# OutputBuffer.net
KiCad netlist of a schematic drawn in Altium Designer
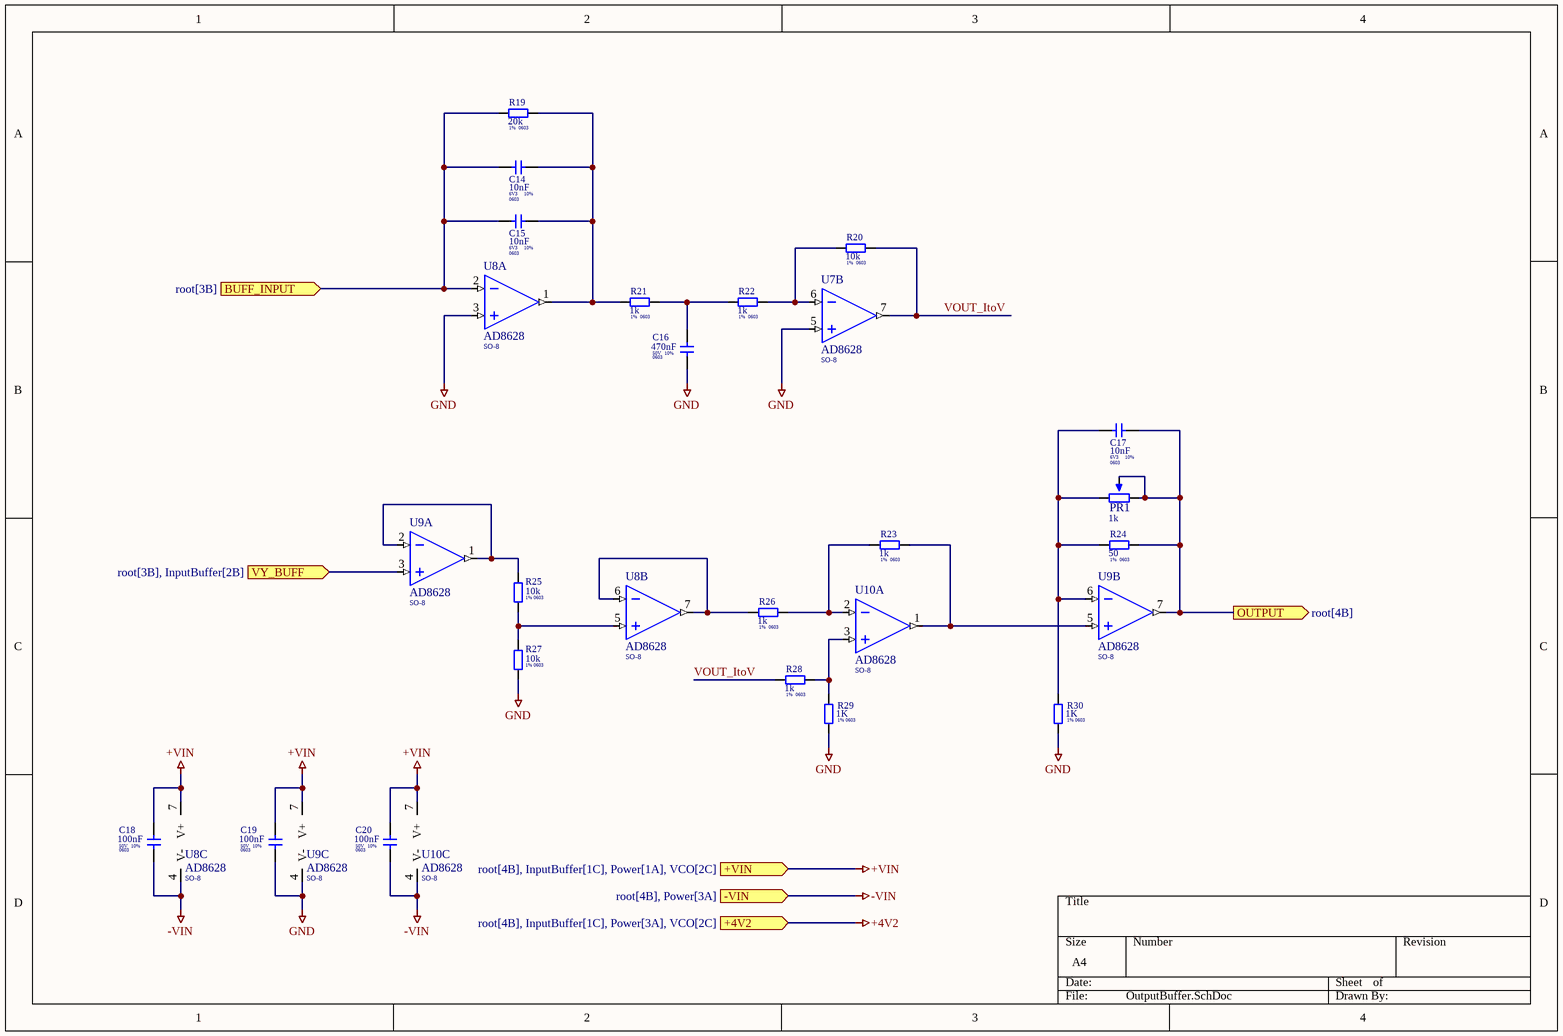
[diagram p0: OutputBuffer.SchDoc]

(export (version "E")
  (design (tool "Eeschema 10.0.6"))
  (components
    (comp (ref "C14")
      (value "10nF")
      (footprint "CAPC1608X06M")
      (fields
        (field (name "VOLTAGE") "6V3")
        (field (name "TOLERANT") "10%")
        (field (name "PACKAGE") "0603")
        (field (name "Comment") "10nF/6V3")
      )
      (libsource (lib "Falcon-SchMain-Lib") (part "C"))
    )
    (comp (ref "C15")
      (value "10nF")
      (footprint "CAPC1608X06M")
      (fields
        (field (name "VOLTAGE") "6V3")
        (field (name "TOLERANT") "10%")
        (field (name "PACKAGE") "0603")
        (field (name "Comment") "10nF/6V3")
      )
      (libsource (lib "Falcon-SchMain-Lib") (part "C"))
    )
    (comp (ref "C16")
      (value "470nF")
      (footprint "CAPC1608X06M")
      (fields
        (field (name "VOLTAGE") "50V")
        (field (name "TOLERANT") "10%")
        (field (name "PACKAGE") "0603")
        (field (name "Comment") "470nF/50V")
      )
      (libsource (lib "Falcon-SchMain-Lib") (part "C"))
    )
    (comp (ref "C17")
      (value "10nF")
      (footprint "CAPC1608X06M")
      (fields
        (field (name "VOLTAGE") "6V3")
        (field (name "TOLERANT") "10%")
        (field (name "PACKAGE") "0603")
        (field (name "Comment") "10nF/6V3")
      )
      (libsource (lib "Falcon-SchMain-Lib") (part "C"))
    )
    (comp (ref "C18")
      (value "100nF")
      (footprint "CAPC1608X06M")
      (fields
        (field (name "VOLTAGE") "50V")
        (field (name "TOLERANT") "10%")
        (field (name "PACKAGE") "0603")
        (field (name "Comment") "100nF/50V")
      )
      (libsource (lib "Falcon-SchMain-Lib") (part "C"))
    )
    (comp (ref "C19")
      (value "100nF")
      (footprint "CAPC1608X06M")
      (fields
        (field (name "VOLTAGE") "50V")
        (field (name "TOLERANT") "10%")
        (field (name "PACKAGE") "0603")
        (field (name "Comment") "100nF/50V")
      )
      (libsource (lib "Falcon-SchMain-Lib") (part "C"))
    )
    (comp (ref "C20")
      (value "100nF")
      (footprint "CAPC1608X06M")
      (fields
        (field (name "VOLTAGE") "50V")
        (field (name "TOLERANT") "10%")
        (field (name "PACKAGE") "0603")
        (field (name "Comment") "100nF/50V")
      )
      (libsource (lib "Falcon-SchMain-Lib") (part "C"))
    )
    (comp (ref "PR1") (value "1k") (footprint "PR_TRIM") (libsource (lib "Falcon-SchMain-Lib") (part "R_PR")))
    (comp (ref "R19")
      (value "20k")
      (footprint "RESC1608X06L")
      (fields
        (field (name "PACKAGE") "0603")
        (field (name "TOLERANCE") "1%")
        (field (name "Comment") "20k 1%")
      )
      (libsource (lib "Falcon-SchMain-Lib") (part "R"))
    )
    (comp (ref "R20")
      (value "10k")
      (footprint "RESC1608X06L")
      (fields
        (field (name "PACKAGE") "0603")
        (field (name "TOLERANCE") "1%")
        (field (name "Comment") "10k 1%")
      )
      (libsource (lib "Falcon-SchMain-Lib") (part "R"))
    )
    (comp (ref "R21")
      (value "1k")
      (footprint "RESC1608X06L")
      (fields
        (field (name "PACKAGE") "0603")
        (field (name "TOLERANCE") "1%")
        (field (name "Comment") "1k 1%")
      )
      (libsource (lib "Falcon-SchMain-Lib") (part "R"))
    )
    (comp (ref "R22")
      (value "1k")
      (footprint "RESC1608X06L")
      (fields
        (field (name "PACKAGE") "0603")
        (field (name "TOLERANCE") "1%")
        (field (name "Comment") "1k 1%")
      )
      (libsource (lib "Falcon-SchMain-Lib") (part "R"))
    )
    (comp (ref "R23")
      (value "1k")
      (footprint "RESC1608X06L")
      (fields
        (field (name "PACKAGE") "0603")
        (field (name "TOLERANCE") "1%")
        (field (name "Comment") "1k 1%")
      )
      (libsource (lib "Falcon-SchMain-Lib") (part "R"))
    )
    (comp (ref "R24")
      (value "50")
      (footprint "RESC1608X06L")
      (fields
        (field (name "PACKAGE") "0603")
        (field (name "TOLERANCE") "1%")
        (field (name "Comment") "50 1%")
      )
      (libsource (lib "Falcon-SchMain-Lib") (part "R"))
    )
    (comp (ref "R25")
      (value "10k")
      (footprint "RESC1608X06L")
      (fields
        (field (name "PACKAGE") "0603")
        (field (name "TOLERANCE") "1%")
        (field (name "Comment") "10k 1%")
      )
      (libsource (lib "") (part "R_1"))
    )
    (comp (ref "R26")
      (value "1k")
      (footprint "RESC1608X06L")
      (fields
        (field (name "PACKAGE") "0603")
        (field (name "TOLERANCE") "1%")
        (field (name "Comment") "1k 1%")
      )
      (libsource (lib "Falcon-SchMain-Lib") (part "R"))
    )
    (comp (ref "R27")
      (value "10k")
      (footprint "RESC1608X06L")
      (fields
        (field (name "PACKAGE") "0603")
        (field (name "TOLERANCE") "1%")
        (field (name "Comment") "10k 1%")
      )
      (libsource (lib "") (part "R_1"))
    )
    (comp (ref "R28")
      (value "1k")
      (footprint "RESC1608X06L")
      (fields
        (field (name "PACKAGE") "0603")
        (field (name "TOLERANCE") "1%")
        (field (name "Comment") "1k 1%")
      )
      (libsource (lib "Falcon-SchMain-Lib") (part "R"))
    )
    (comp (ref "R29")
      (value "1K")
      (footprint "RESC1608X06L")
      (fields
        (field (name "PACKAGE") "0603")
        (field (name "TOLERANCE") "1%")
        (field (name "Comment") "1K 1%")
      )
      (libsource (lib "") (part "R_1"))
    )
    (comp (ref "R30")
      (value "1K")
      (footprint "RESC1608X06L")
      (fields
        (field (name "PACKAGE") "0603")
        (field (name "TOLERANCE") "1%")
        (field (name "Comment") "1K 1%")
      )
      (libsource (lib "") (part "R_1"))
    )
    (comp (ref "U7")
      (value "AD8628")
      (footprint "SOIC127P600X170-8N")
      (description "Zero-Drift, Single-Supply, Rail-to-Rail Input/Output Operational Amplifier")
      (fields (field (name "PACKAGE") "SO-8"))
      (libsource (lib "Falcon-SchMain-Lib") (part "AD8628ARZ"))
    )
    (comp (ref "U8")
      (value "AD8628")
      (footprint "SOIC127P600X170-8N")
      (description "Zero-Drift, Single-Supply, Rail-to-Rail Input/Output Operational Amplifier")
      (fields (field (name "PACKAGE") "SO-8"))
      (libsource (lib "Falcon-SchMain-Lib") (part "AD8628ARZ"))
    )
    (comp (ref "U9")
      (value "AD8628")
      (footprint "SOIC127P600X170-8N")
      (description "Zero-Drift, Single-Supply, Rail-to-Rail Input/Output Operational Amplifier")
      (fields (field (name "PACKAGE") "SO-8"))
      (libsource (lib "Falcon-SchMain-Lib") (part "AD8628ARZ"))
    )
    (comp (ref "U10")
      (value "AD8628")
      (footprint "SOIC127P600X170-8N")
      (description "Zero-Drift, Single-Supply, Rail-to-Rail Input/Output Operational Amplifier")
      (fields (field (name "PACKAGE") "SO-8"))
      (libsource (lib "Falcon-SchMain-Lib") (part "AD8628ARZ"))
    )
  )
  (nets
    (net (code "2") (name "+VIN") (class "Default")
      (node (ref "C18") (pin "2") (pinfunction "2_2") (pintype "passive"))
      (node (ref "C19") (pin "2") (pinfunction "2_2") (pintype "passive"))
      (node (ref "C20") (pin "2") (pinfunction "2_2") (pintype "passive"))
      (node (ref "U10") (pin "7") (pinfunction "V+_7") (pintype "power_in"))
      (node (ref "U8") (pin "7") (pinfunction "V+_7") (pintype "power_in"))
      (node (ref "U9") (pin "7") (pinfunction "V+_7") (pintype "power_in"))
    )
    (net (code "3") (name "-VIN") (class "Default")
      (node (ref "C18") (pin "1") (pinfunction "1_1") (pintype "passive"))
      (node (ref "C20") (pin "1") (pinfunction "1_1") (pintype "passive"))
      (node (ref "U10") (pin "4") (pinfunction "V-_4") (pintype "power_in"))
      (node (ref "U8") (pin "4") (pinfunction "V-_4") (pintype "power_in"))
    )
    (net (code "4") (name "/BUFF_INPUT") (class "Default")
      (node (ref "C14") (pin "1") (pinfunction "1_1") (pintype "passive"))
      (node (ref "C15") (pin "1") (pinfunction "1_1") (pintype "passive"))
      (node (ref "R19") (pin "1") (pinfunction "1_1") (pintype "passive"))
      (node (ref "U8") (pin "2") (pinfunction "IN-_2") (pintype "input"))
    )
    (net (code "5") (name "/OUTPUT") (class "Default")
      (node (ref "C17") (pin "2") (pinfunction "2_2") (pintype "passive"))
      (node (ref "PR1") (pin "2") (pinfunction "2_2") (pintype "power_in"))
      (node (ref "PR1") (pin "3") (pinfunction "3_3") (pintype "passive"))
      (node (ref "R24") (pin "2") (pinfunction "2_2") (pintype "passive"))
      (node (ref "U9") (pin "7") (pinfunction "OUT_7") (pintype "output"))
    )
    (net (code "6") (name "/VOUT_ItoV") (class "Default")
      (node (ref "R20") (pin "2") (pinfunction "2_2") (pintype "passive"))
      (node (ref "R28") (pin "1") (pinfunction "1_1") (pintype "passive"))
      (node (ref "U7") (pin "7") (pinfunction "OUT_7") (pintype "output"))
    )
    (net (code "7") (name "/VY_BUFF") (class "Default")
      (node (ref "U9") (pin "3") (pinfunction "IN+_3") (pintype "input"))
    )
    (net (code "8") (name "GND") (class "Default")
      (node (ref "C16") (pin "1") (pinfunction "1_1") (pintype "passive"))
      (node (ref "C19") (pin "1") (pinfunction "1_1") (pintype "passive"))
      (node (ref "R27") (pin "1") (pinfunction "1_1") (pintype "passive"))
      (node (ref "R29") (pin "1") (pinfunction "1_1") (pintype "passive"))
      (node (ref "R30") (pin "1") (pinfunction "1_1") (pintype "passive"))
      (node (ref "U7") (pin "5") (pinfunction "IN+_5") (pintype "input"))
      (node (ref "U8") (pin "3") (pinfunction "IN+_3") (pintype "input"))
      (node (ref "U9") (pin "4") (pinfunction "V-_4") (pintype "power_in"))
    )
    (net (code "9") (name "Net-(C16-Pad2)") (class "Default")
      (node (ref "C16") (pin "2") (pinfunction "2_2") (pintype "passive"))
      (node (ref "R21") (pin "2") (pinfunction "2_2") (pintype "passive"))
      (node (ref "R22") (pin "1") (pinfunction "1_1") (pintype "passive"))
    )
    (net (code "10") (name "Net-(U7B-IN-)") (class "Default")
      (node (ref "R20") (pin "1") (pinfunction "1_1") (pintype "passive"))
      (node (ref "R22") (pin "2") (pinfunction "2_2") (pintype "passive"))
      (node (ref "U7") (pin "6") (pinfunction "IN-_6") (pintype "input"))
    )
    (net (code "11") (name "Net-(U8A-OUT)") (class "Default")
      (node (ref "C14") (pin "2") (pinfunction "2_2") (pintype "passive"))
      (node (ref "C15") (pin "2") (pinfunction "2_2") (pintype "passive"))
      (node (ref "R19") (pin "2") (pinfunction "2_2") (pintype "passive"))
      (node (ref "R21") (pin "1") (pinfunction "1_1") (pintype "passive"))
      (node (ref "U8") (pin "1") (pinfunction "OUT_1") (pintype "output"))
    )
    (net (code "12") (name "Net-(U8B-IN+)") (class "Default")
      (node (ref "R25") (pin "1") (pinfunction "1_1") (pintype "passive"))
      (node (ref "R27") (pin "2") (pinfunction "2_2") (pintype "passive"))
      (node (ref "U8") (pin "5") (pinfunction "IN+_5") (pintype "input"))
    )
    (net (code "13") (name "Net-(U8B-IN-)") (class "Default")
      (node (ref "R26") (pin "1") (pinfunction "1_1") (pintype "passive"))
      (node (ref "U8") (pin "6") (pinfunction "IN-_6") (pintype "input"))
      (node (ref "U8") (pin "7") (pinfunction "OUT_7") (pintype "output"))
    )
    (net (code "14") (name "Net-(U9A-IN-)") (class "Default")
      (node (ref "R25") (pin "2") (pinfunction "2_2") (pintype "passive"))
      (node (ref "U9") (pin "1") (pinfunction "OUT_1") (pintype "output"))
      (node (ref "U9") (pin "2") (pinfunction "IN-_2") (pintype "input"))
    )
    (net (code "15") (name "Net-(U9B-IN-)") (class "Default")
      (node (ref "C17") (pin "1") (pinfunction "1_1") (pintype "passive"))
      (node (ref "PR1") (pin "1") (pinfunction "1_1") (pintype "passive"))
      (node (ref "R24") (pin "1") (pinfunction "1_1") (pintype "passive"))
      (node (ref "R30") (pin "2") (pinfunction "2_2") (pintype "passive"))
      (node (ref "U9") (pin "6") (pinfunction "IN-_6") (pintype "input"))
    )
    (net (code "16") (name "Net-(U10A-IN+)") (class "Default")
      (node (ref "R28") (pin "2") (pinfunction "2_2") (pintype "passive"))
      (node (ref "R29") (pin "2") (pinfunction "2_2") (pintype "passive"))
      (node (ref "U10") (pin "3") (pinfunction "IN+_3") (pintype "input"))
    )
    (net (code "17") (name "Net-(U10A-IN-)") (class "Default")
      (node (ref "R23") (pin "1") (pinfunction "1_1") (pintype "passive"))
      (node (ref "R26") (pin "2") (pinfunction "2_2") (pintype "passive"))
      (node (ref "U10") (pin "2") (pinfunction "IN-_2") (pintype "input"))
    )
    (net (code "18") (name "Net-(U10A-OUT)") (class "Default")
      (node (ref "R23") (pin "2") (pinfunction "2_2") (pintype "passive"))
      (node (ref "U10") (pin "1") (pinfunction "OUT_1") (pintype "output"))
      (node (ref "U9") (pin "5") (pinfunction "IN+_5") (pintype "input"))
    )
  )
)
